# power_distribution.net
KiCad netlist of a schematic drawn in EAGLE
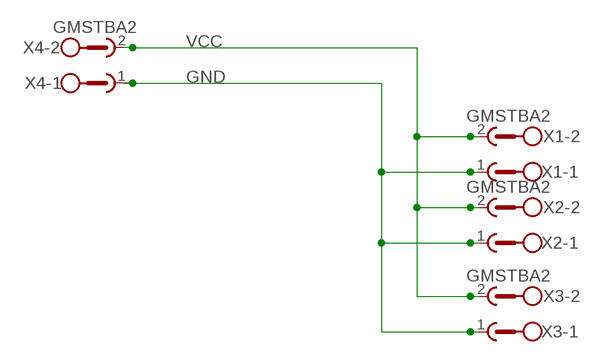
[diagram p0: schematic, sheet 1]

(export (version "E")
  (design (tool "Eeschema 10.0.6"))
  (components
    (comp (ref "X1")
      (value "GMSTBA2")
      (footprint "eagle-import:GMSTBA2")
      (fields (field (name "MF") "FARNELL") (field (name "MPN") "1757242"))
      (libsource (lib "eagle-import") (part "GMSTBA2"))
    )
    (comp (ref "X2")
      (value "GMSTBA2")
      (footprint "eagle-import:GMSTBA2")
      (fields (field (name "MF") "FARNELL") (field (name "MPN") "1757242"))
      (libsource (lib "eagle-import") (part "GMSTBA2"))
    )
    (comp (ref "X3")
      (value "GMSTBA2")
      (footprint "eagle-import:GMSTBA2")
      (fields (field (name "MF") "FARNELL") (field (name "MPN") "1757242"))
      (libsource (lib "eagle-import") (part "GMSTBA2"))
    )
    (comp (ref "X4")
      (value "GMSTBA2")
      (footprint "eagle-import:GMSTBA2")
      (fields (field (name "MF") "FARNELL") (field (name "MPN") "1757242"))
      (libsource (lib "eagle-import") (part "GMSTBA2"))
    )
  )
  (nets
    (net (code "1") (name "/GND") (class "Default")
      (node (ref "X1") (pin "1") (pinfunction "1_1") (pintype "passive"))
      (node (ref "X2") (pin "1") (pinfunction "1_1") (pintype "passive"))
      (node (ref "X3") (pin "1") (pinfunction "1_1") (pintype "passive"))
      (node (ref "X4") (pin "1") (pinfunction "1_1") (pintype "passive"))
    )
    (net (code "2") (name "/VCC") (class "Default")
      (node (ref "X1") (pin "2") (pinfunction "1_2") (pintype "passive"))
      (node (ref "X2") (pin "2") (pinfunction "1_2") (pintype "passive"))
      (node (ref "X3") (pin "2") (pinfunction "1_2") (pintype "passive"))
      (node (ref "X4") (pin "2") (pinfunction "1_2") (pintype "passive"))
    )
  )
)
